# STM32.net
KiCad netlist of a schematic drawn in Altium Designer
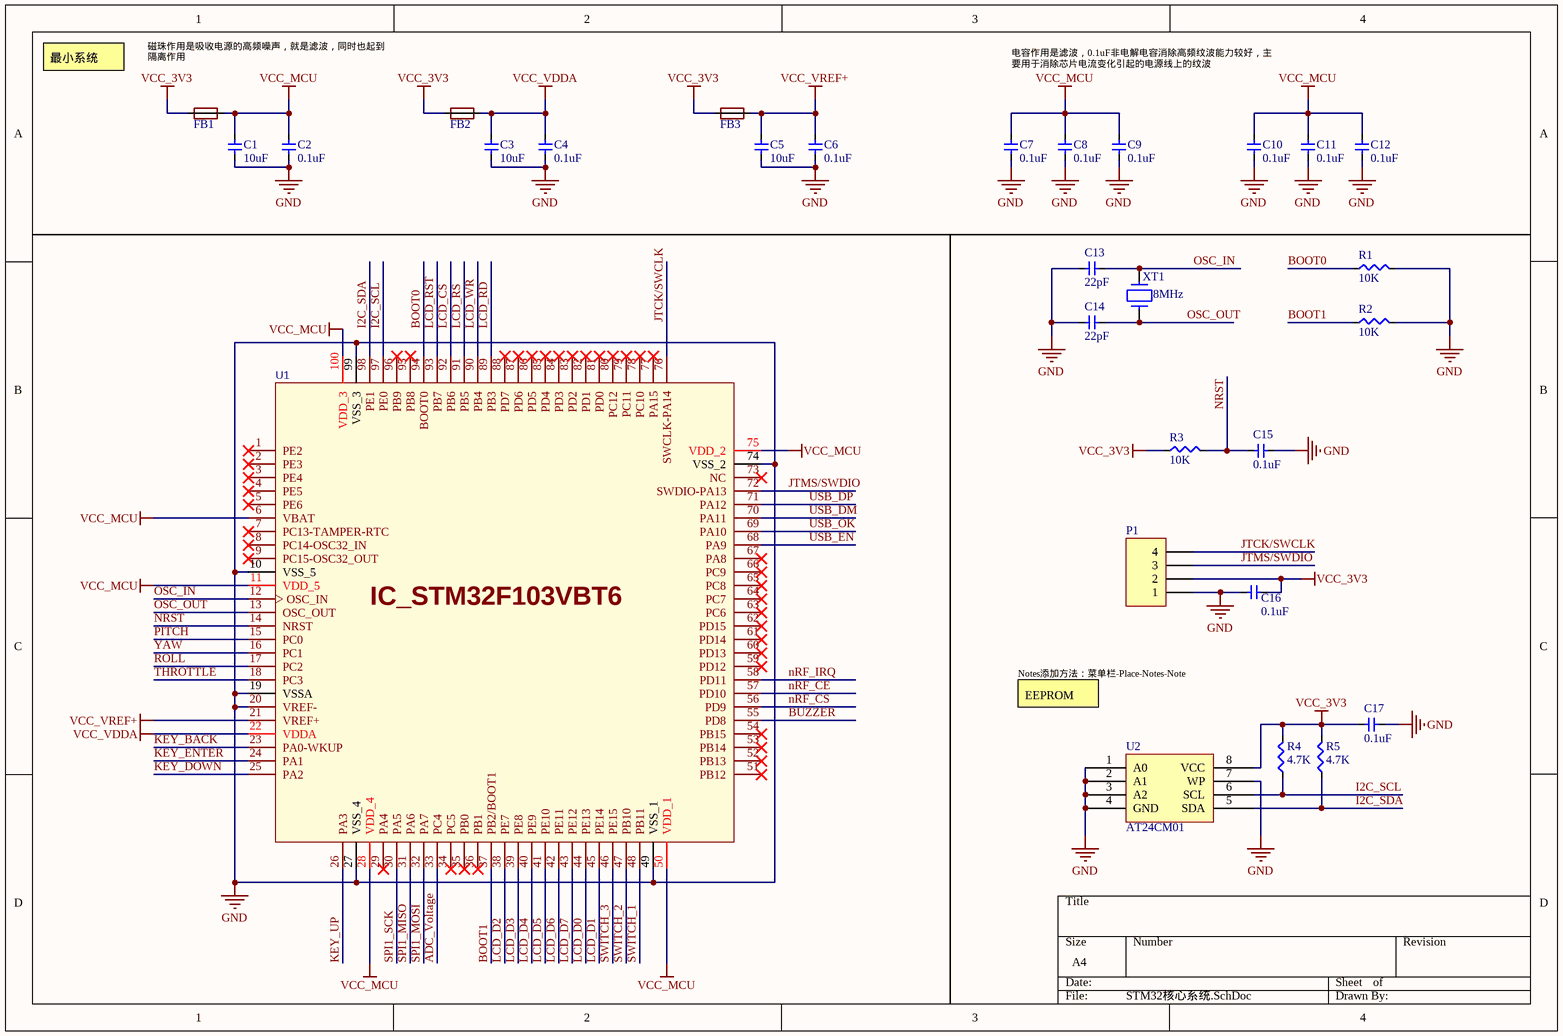
[diagram p0: STM32核心系统.SchDoc]

(export (version "E")
  (design (tool "Eeschema 10.0.6"))
  (components
    (comp (ref "C1")
      (value "10uF")
      (footprint "C 0603_L")
      (description "电容")
      (libsource (lib "SCHLIB") (part "CX_CAP"))
    )
    (comp (ref "C2")
      (value "0.1uF")
      (footprint "C 0603_L")
      (description "电容")
      (libsource (lib "SCHLIB") (part "CX_CAP"))
    )
    (comp (ref "C3")
      (value "10uF")
      (footprint "C 0603_L")
      (description "电容")
      (libsource (lib "SCHLIB") (part "CX_CAP"))
    )
    (comp (ref "C4")
      (value "0.1uF")
      (footprint "C 0603_L")
      (description "电容")
      (libsource (lib "SCHLIB") (part "CX_CAP"))
    )
    (comp (ref "C5")
      (value "10uF")
      (footprint "C 0603_L")
      (description "电容")
      (libsource (lib "SCHLIB") (part "CX_CAP"))
    )
    (comp (ref "C6")
      (value "0.1uF")
      (footprint "C 0603_L")
      (description "电容")
      (libsource (lib "SCHLIB") (part "CX_CAP"))
    )
    (comp (ref "C7")
      (value "0.1uF")
      (footprint "C 0603_L")
      (description "电容")
      (libsource (lib "SCHLIB") (part "CX_CAP"))
    )
    (comp (ref "C8")
      (value "0.1uF")
      (footprint "C 0603_L")
      (description "电容")
      (libsource (lib "SCHLIB") (part "CX_CAP"))
    )
    (comp (ref "C9")
      (value "0.1uF")
      (footprint "C 0603_L")
      (description "电容")
      (libsource (lib "SCHLIB") (part "CX_CAP"))
    )
    (comp (ref "C10")
      (value "0.1uF")
      (footprint "C 0603_L")
      (description "电容")
      (libsource (lib "SCHLIB") (part "CX_CAP"))
    )
    (comp (ref "C11")
      (value "0.1uF")
      (footprint "C 0603_L")
      (description "电容")
      (libsource (lib "SCHLIB") (part "CX_CAP"))
    )
    (comp (ref "C12")
      (value "0.1uF")
      (footprint "C 0603_L")
      (description "电容")
      (libsource (lib "SCHLIB") (part "CX_CAP"))
    )
    (comp (ref "C13")
      (value "22pF")
      (footprint "C 0603_L")
      (description "电容")
      (libsource (lib "SCHLIB") (part "CX_CAP"))
    )
    (comp (ref "C14")
      (value "22pF")
      (footprint "C 0603_L")
      (description "电容")
      (libsource (lib "SCHLIB") (part "CX_CAP"))
    )
    (comp (ref "C15")
      (value "0.1uF")
      (footprint "C 0603_L")
      (description "电容")
      (libsource (lib "SCHLIB") (part "CX_CAP"))
    )
    (comp (ref "C16")
      (value "0.1uF")
      (footprint "C 0603_L")
      (description "电容")
      (libsource (lib "SCHLIB") (part "CX_CAP"))
    )
    (comp (ref "C17")
      (value "0.1uF")
      (footprint "C 0603_L")
      (description "电容")
      (libsource (lib "SCHLIB") (part "CX_CAP"))
    )
    (comp (ref "FB1")
      (value "FB_BEAD")
      (footprint "FB 0603_L")
      (description "磁珠")
      (libsource (lib "MySCHLIB") (part "FB_BEAD"))
    )
    (comp (ref "FB2")
      (value "FB_BEAD")
      (footprint "FB 0603_L")
      (description "磁珠")
      (libsource (lib "MySCHLIB") (part "FB_BEAD"))
    )
    (comp (ref "FB3")
      (value "FB_BEAD")
      (footprint "FB 0603_L")
      (description "磁珠")
      (libsource (lib "MySCHLIB") (part "FB_BEAD"))
    )
    (comp (ref "P1")
      (value "Header 4")
      (footprint "XH2.54-WI-4P")
      (description "Header, 4-Pin")
      (fields (field (name "PUBLISHER") "Altium Limited"))
      (libsource (lib "Miscellaneous Connectors") (part "Header 4"))
    )
    (comp (ref "R1")
      (value "10K")
      (footprint "R 0603_L")
      (description "电阻")
      (libsource (lib "SCHLIB") (part "RX_RES"))
    )
    (comp (ref "R2")
      (value "10K")
      (footprint "R 0603_L")
      (description "电阻")
      (libsource (lib "SCHLIB") (part "RX_RES"))
    )
    (comp (ref "R3")
      (value "10K")
      (footprint "R 0603_L")
      (description "电阻")
      (libsource (lib "SCHLIB") (part "RX_RES"))
    )
    (comp (ref "R4")
      (value "4.7K")
      (footprint "R 0603_L")
      (description "电阻")
      (libsource (lib "SCHLIB") (part "RX_RES"))
    )
    (comp (ref "R5")
      (value "4.7K")
      (footprint "R 0603_L")
      (description "电阻")
      (libsource (lib "SCHLIB") (part "RX_RES"))
    )
    (comp (ref "U1")
      (value "IC_STM32F103VBT6")
      (footprint "LQFP100 14x14_M")
      (description "STM32单片机")
      (fields
        (field (name "BOM_SUPPLIER PART") "C8314")
        (field (name "BOM_MANUFACTURER PART") "STM32F103VBT6")
      )
      (libsource (lib "SCHLIB") (part "IC_STM32F103VBT6"))
    )
    (comp (ref "U2")
      (value "AT24CM01")
      (footprint "SOIC-8")
      (description "存储芯片")
      (libsource (lib "SCHLIB") (part "IC_AT24C02"))
    )
    (comp (ref "XT1")
      (value "8MHz")
      (footprint "OSC 5032-2P")
      (description "2P晶振")
      (fields (field (name "Comment") "XT_CRYSTAL2P"))
      (libsource (lib "SCHLIB") (part "XT_CRYSTAL2P"))
    )
  )
  (nets
    (net (code "1") (name "/ADC_Voltage") (class "Default")
      (node (ref "U1") (pin "33") (pinfunction "PC4_33") (pintype "passive"))
    )
    (net (code "2") (name "/BOOT0") (class "Default")
      (node (ref "R1") (pin "1") (pinfunction "1_1") (pintype "passive"))
      (node (ref "U1") (pin "94") (pinfunction "BOOT0_94") (pintype "passive"))
    )
    (net (code "3") (name "/BOOT1") (class "Default")
      (node (ref "R2") (pin "1") (pinfunction "1_1") (pintype "passive"))
      (node (ref "U1") (pin "37") (pinfunction "PB2/BOOT1_37") (pintype "passive"))
    )
    (net (code "4") (name "/BUZZER") (class "Default")
      (node (ref "U1") (pin "55") (pinfunction "PD8_55") (pintype "passive"))
    )
    (net (code "5") (name "/I2C_SCL") (class "Default")
      (node (ref "R4") (pin "1") (pinfunction "1_1") (pintype "passive"))
      (node (ref "U1") (pin "97") (pinfunction "PE0_97") (pintype "passive"))
      (node (ref "U2") (pin "6") (pinfunction "SCL_6") (pintype "passive"))
    )
    (net (code "6") (name "/I2C_SDA") (class "Default")
      (node (ref "R5") (pin "1") (pinfunction "1_1") (pintype "passive"))
      (node (ref "U1") (pin "98") (pinfunction "PE1_98") (pintype "passive"))
      (node (ref "U2") (pin "5") (pinfunction "SDA_5") (pintype "passive"))
    )
    (net (code "7") (name "/JTCK{slash}SWCLK") (class "Default")
      (node (ref "P1") (pin "4") (pinfunction "4_4") (pintype "passive"))
      (node (ref "U1") (pin "76") (pinfunction "SWCLK-PA14_76") (pintype "passive"))
    )
    (net (code "8") (name "/JTMS{slash}SWDIO") (class "Default")
      (node (ref "P1") (pin "3") (pinfunction "3_3") (pintype "passive"))
      (node (ref "U1") (pin "72") (pinfunction "SWDIO-PA13_72") (pintype "passive"))
    )
    (net (code "9") (name "/KEY_BACK") (class "Default")
      (node (ref "U1") (pin "23") (pinfunction "PA0-WKUP_23") (pintype "passive"))
    )
    (net (code "10") (name "/KEY_DOWN") (class "Default")
      (node (ref "U1") (pin "25") (pinfunction "PA2_25") (pintype "passive"))
    )
    (net (code "11") (name "/KEY_ENTER") (class "Default")
      (node (ref "U1") (pin "24") (pinfunction "PA1_24") (pintype "passive"))
    )
    (net (code "12") (name "/KEY_UP") (class "Default")
      (node (ref "U1") (pin "26") (pinfunction "PA3_26") (pintype "passive"))
    )
    (net (code "13") (name "/LCD_CS") (class "Default")
      (node (ref "U1") (pin "92") (pinfunction "PB6_92") (pintype "passive"))
    )
    (net (code "14") (name "/LCD_D0") (class "Default")
      (node (ref "U1") (pin "44") (pinfunction "PE13_44") (pintype "passive"))
    )
    (net (code "15") (name "/LCD_D1") (class "Default")
      (node (ref "U1") (pin "45") (pinfunction "PE14_45") (pintype "passive"))
    )
    (net (code "16") (name "/LCD_D2") (class "Default")
      (node (ref "U1") (pin "38") (pinfunction "PE7_38") (pintype "passive"))
    )
    (net (code "17") (name "/LCD_D3") (class "Default")
      (node (ref "U1") (pin "39") (pinfunction "PE8_39") (pintype "passive"))
    )
    (net (code "18") (name "/LCD_D4") (class "Default")
      (node (ref "U1") (pin "40") (pinfunction "PE9_40") (pintype "passive"))
    )
    (net (code "19") (name "/LCD_D5") (class "Default")
      (node (ref "U1") (pin "41") (pinfunction "PE10_41") (pintype "passive"))
    )
    (net (code "20") (name "/LCD_D6") (class "Default")
      (node (ref "U1") (pin "42") (pinfunction "PE11_42") (pintype "passive"))
    )
    (net (code "21") (name "/LCD_D7") (class "Default")
      (node (ref "U1") (pin "43") (pinfunction "PE12_43") (pintype "passive"))
    )
    (net (code "22") (name "/LCD_RD") (class "Default")
      (node (ref "U1") (pin "89") (pinfunction "PB3_89") (pintype "passive"))
    )
    (net (code "23") (name "/LCD_RS") (class "Default")
      (node (ref "U1") (pin "91") (pinfunction "PB5_91") (pintype "passive"))
    )
    (net (code "24") (name "/LCD_RST") (class "Default")
      (node (ref "U1") (pin "93") (pinfunction "PB7_93") (pintype "passive"))
    )
    (net (code "25") (name "/LCD_WR") (class "Default")
      (node (ref "U1") (pin "90") (pinfunction "PB4_90") (pintype "passive"))
    )
    (net (code "26") (name "/NRST") (class "Default")
      (node (ref "C15") (pin "1") (pinfunction "1_1") (pintype "passive"))
      (node (ref "R3") (pin "2") (pinfunction "2_2") (pintype "passive"))
      (node (ref "U1") (pin "14") (pinfunction "NRST_14") (pintype "passive"))
    )
    (net (code "27") (name "/OSC_IN") (class "Default")
      (node (ref "C13") (pin "2") (pinfunction "2_2") (pintype "passive"))
      (node (ref "U1") (pin "12") (pinfunction "OSC_IN_12") (pintype "passive"))
      (node (ref "XT1") (pin "2") (pinfunction "2_2") (pintype "passive"))
    )
    (net (code "28") (name "/OSC_OUT") (class "Default")
      (node (ref "C14") (pin "2") (pinfunction "2_2") (pintype "passive"))
      (node (ref "U1") (pin "13") (pinfunction "OSC_OUT_13") (pintype "passive"))
      (node (ref "XT1") (pin "1") (pinfunction "1_1") (pintype "passive"))
    )
    (net (code "29") (name "/PITCH") (class "Default")
      (node (ref "U1") (pin "15") (pinfunction "PC0_15") (pintype "passive"))
    )
    (net (code "30") (name "/ROLL") (class "Default")
      (node (ref "U1") (pin "17") (pinfunction "PC2_17") (pintype "passive"))
    )
    (net (code "31") (name "/SPI1_MISO") (class "Default")
      (node (ref "U1") (pin "31") (pinfunction "PA6_31") (pintype "passive"))
    )
    (net (code "32") (name "/SPI1_MOSI") (class "Default")
      (node (ref "U1") (pin "32") (pinfunction "PA7_32") (pintype "passive"))
    )
    (net (code "33") (name "/SPI1_SCK") (class "Default")
      (node (ref "U1") (pin "30") (pinfunction "PA5_30") (pintype "passive"))
    )
    (net (code "34") (name "/SWITCH_1") (class "Default")
      (node (ref "U1") (pin "48") (pinfunction "PB11_48") (pintype "passive"))
    )
    (net (code "35") (name "/SWITCH_2") (class "Default")
      (node (ref "U1") (pin "47") (pinfunction "PB10_47") (pintype "passive"))
    )
    (net (code "36") (name "/SWITCH_3") (class "Default")
      (node (ref "U1") (pin "46") (pinfunction "PE15_46") (pintype "passive"))
    )
    (net (code "37") (name "/THROTTLE") (class "Default")
      (node (ref "U1") (pin "18") (pinfunction "PC3_18") (pintype "passive"))
    )
    (net (code "38") (name "/USB_DM") (class "Default")
      (node (ref "U1") (pin "70") (pinfunction "PA11_70") (pintype "passive"))
    )
    (net (code "39") (name "/USB_DP") (class "Default")
      (node (ref "U1") (pin "71") (pinfunction "PA12_71") (pintype "passive"))
    )
    (net (code "40") (name "/USB_EN") (class "Default")
      (node (ref "U1") (pin "68") (pinfunction "PA9_68") (pintype "passive"))
    )
    (net (code "41") (name "/USB_OK") (class "Default")
      (node (ref "U1") (pin "69") (pinfunction "PA10_69") (pintype "passive"))
    )
    (net (code "42") (name "/YAW") (class "Default")
      (node (ref "U1") (pin "16") (pinfunction "PC1_16") (pintype "passive"))
    )
    (net (code "43") (name "/nRF_CE") (class "Default")
      (node (ref "U1") (pin "57") (pinfunction "PD10_57") (pintype "passive"))
    )
    (net (code "44") (name "/nRF_CS") (class "Default")
      (node (ref "U1") (pin "56") (pinfunction "PD9_56") (pintype "passive"))
    )
    (net (code "45") (name "/nRF_IRQ") (class "Default")
      (node (ref "U1") (pin "58") (pinfunction "PD11_58") (pintype "passive"))
    )
    (net (code "46") (name "GND") (class "Default")
      (node (ref "C1") (pin "2") (pinfunction "2_2") (pintype "passive"))
      (node (ref "C10") (pin "2") (pinfunction "2_2") (pintype "passive"))
      (node (ref "C11") (pin "2") (pinfunction "2_2") (pintype "passive"))
      (node (ref "C12") (pin "2") (pinfunction "2_2") (pintype "passive"))
      (node (ref "C13") (pin "1") (pinfunction "1_1") (pintype "passive"))
      (node (ref "C14") (pin "1") (pinfunction "1_1") (pintype "passive"))
      (node (ref "C15") (pin "2") (pinfunction "2_2") (pintype "passive"))
      (node (ref "C16") (pin "1") (pinfunction "1_1") (pintype "passive"))
      (node (ref "C17") (pin "2") (pinfunction "2_2") (pintype "passive"))
      (node (ref "C2") (pin "2") (pinfunction "2_2") (pintype "passive"))
      (node (ref "C3") (pin "2") (pinfunction "2_2") (pintype "passive"))
      (node (ref "C4") (pin "2") (pinfunction "2_2") (pintype "passive"))
      (node (ref "C5") (pin "2") (pinfunction "2_2") (pintype "passive"))
      (node (ref "C6") (pin "2") (pinfunction "2_2") (pintype "passive"))
      (node (ref "C7") (pin "2") (pinfunction "2_2") (pintype "passive"))
      (node (ref "C8") (pin "2") (pinfunction "2_2") (pintype "passive"))
      (node (ref "C9") (pin "2") (pinfunction "2_2") (pintype "passive"))
      (node (ref "P1") (pin "1") (pinfunction "1_1") (pintype "passive"))
      (node (ref "R1") (pin "2") (pinfunction "2_2") (pintype "passive"))
      (node (ref "R2") (pin "2") (pinfunction "2_2") (pintype "passive"))
      (node (ref "U1") (pin "10") (pinfunction "VSS_5_10") (pintype "passive"))
      (node (ref "U1") (pin "19") (pinfunction "VSSA_19") (pintype "passive"))
      (node (ref "U1") (pin "20") (pinfunction "VREF-_20") (pintype "passive"))
      (node (ref "U1") (pin "27") (pinfunction "VSS_4_27") (pintype "passive"))
      (node (ref "U1") (pin "49") (pinfunction "VSS_1_49") (pintype "passive"))
      (node (ref "U1") (pin "74") (pinfunction "VSS_2_74") (pintype "passive"))
      (node (ref "U1") (pin "99") (pinfunction "VSS_3_99") (pintype "passive"))
      (node (ref "U2") (pin "1") (pinfunction "A0_1") (pintype "passive"))
      (node (ref "U2") (pin "2") (pinfunction "A1_2") (pintype "passive"))
      (node (ref "U2") (pin "3") (pinfunction "A2_3") (pintype "passive"))
      (node (ref "U2") (pin "4") (pinfunction "GND_4") (pintype "passive"))
      (node (ref "U2") (pin "7") (pinfunction "WP_7") (pintype "passive"))
    )
    (net (code "47") (name "VCC_3V3") (class "Default")
      (node (ref "C16") (pin "2") (pinfunction "2_2") (pintype "passive"))
      (node (ref "C17") (pin "1") (pinfunction "1_1") (pintype "passive"))
      (node (ref "FB1") (pin "2") (pinfunction "2_2") (pintype "passive"))
      (node (ref "FB2") (pin "2") (pinfunction "2_2") (pintype "passive"))
      (node (ref "FB3") (pin "2") (pinfunction "2_2") (pintype "passive"))
      (node (ref "P1") (pin "2") (pinfunction "2_2") (pintype "passive"))
      (node (ref "R3") (pin "1") (pinfunction "1_1") (pintype "passive"))
      (node (ref "R4") (pin "2") (pinfunction "2_2") (pintype "passive"))
      (node (ref "R5") (pin "2") (pinfunction "2_2") (pintype "passive"))
      (node (ref "U2") (pin "8") (pinfunction "VCC_8") (pintype "passive"))
    )
    (net (code "48") (name "VCC_MCU") (class "Default")
      (node (ref "C1") (pin "1") (pinfunction "1_1") (pintype "passive"))
      (node (ref "C10") (pin "1") (pinfunction "1_1") (pintype "passive"))
      (node (ref "C11") (pin "1") (pinfunction "1_1") (pintype "passive"))
      (node (ref "C12") (pin "1") (pinfunction "1_1") (pintype "passive"))
      (node (ref "C2") (pin "1") (pinfunction "1_1") (pintype "passive"))
      (node (ref "C7") (pin "1") (pinfunction "1_1") (pintype "passive"))
      (node (ref "C8") (pin "1") (pinfunction "1_1") (pintype "passive"))
      (node (ref "C9") (pin "1") (pinfunction "1_1") (pintype "passive"))
      (node (ref "FB1") (pin "1") (pinfunction "1_1") (pintype "passive"))
      (node (ref "U1") (pin "100") (pinfunction "VDD_3_100") (pintype "passive"))
      (node (ref "U1") (pin "11") (pinfunction "VDD_5_11") (pintype "passive"))
      (node (ref "U1") (pin "28") (pinfunction "VDD_4_28") (pintype "passive"))
      (node (ref "U1") (pin "50") (pinfunction "VDD_1_50") (pintype "passive"))
      (node (ref "U1") (pin "6") (pinfunction "VBAT_6") (pintype "passive"))
      (node (ref "U1") (pin "75") (pinfunction "VDD_2_75") (pintype "passive"))
    )
    (net (code "49") (name "VCC_VDDA") (class "Default")
      (node (ref "C3") (pin "1") (pinfunction "1_1") (pintype "passive"))
      (node (ref "C4") (pin "1") (pinfunction "1_1") (pintype "passive"))
      (node (ref "FB2") (pin "1") (pinfunction "1_1") (pintype "passive"))
      (node (ref "U1") (pin "22") (pinfunction "VDDA_22") (pintype "passive"))
    )
    (net (code "50") (name "VCC_VREF+") (class "Default")
      (node (ref "C5") (pin "1") (pinfunction "1_1") (pintype "passive"))
      (node (ref "C6") (pin "1") (pinfunction "1_1") (pintype "passive"))
      (node (ref "FB3") (pin "1") (pinfunction "1_1") (pintype "passive"))
      (node (ref "U1") (pin "21") (pinfunction "VREF+_21") (pintype "passive"))
    )
    (net (code "51") (name "unconnected-(U1-NC-Pad73)") (class "Default")
      (node (ref "U1") (pin "73") (pinfunction "NC_73") (pintype "passive+no_connect"))
    )
    (net (code "52") (name "unconnected-(U1-PA4-Pad29)") (class "Default")
      (node (ref "U1") (pin "29") (pinfunction "PA4_29") (pintype "passive+no_connect"))
    )
    (net (code "53") (name "unconnected-(U1-PA8-Pad67)") (class "Default")
      (node (ref "U1") (pin "67") (pinfunction "PA8_67") (pintype "passive+no_connect"))
    )
    (net (code "54") (name "unconnected-(U1-PA15-Pad77)") (class "Default")
      (node (ref "U1") (pin "77") (pinfunction "PA15_77") (pintype "passive+no_connect"))
    )
    (net (code "55") (name "unconnected-(U1-PB0-Pad35)") (class "Default")
      (node (ref "U1") (pin "35") (pinfunction "PB0_35") (pintype "passive+no_connect"))
    )
    (net (code "56") (name "unconnected-(U1-PB1-Pad36)") (class "Default")
      (node (ref "U1") (pin "36") (pinfunction "PB1_36") (pintype "passive+no_connect"))
    )
    (net (code "57") (name "unconnected-(U1-PB8-Pad95)") (class "Default")
      (node (ref "U1") (pin "95") (pinfunction "PB8_95") (pintype "passive+no_connect"))
    )
    (net (code "58") (name "unconnected-(U1-PB9-Pad96)") (class "Default")
      (node (ref "U1") (pin "96") (pinfunction "PB9_96") (pintype "passive+no_connect"))
    )
    (net (code "59") (name "unconnected-(U1-PB12-Pad51)") (class "Default")
      (node (ref "U1") (pin "51") (pinfunction "PB12_51") (pintype "passive+no_connect"))
    )
    (net (code "60") (name "unconnected-(U1-PB13-Pad52)") (class "Default")
      (node (ref "U1") (pin "52") (pinfunction "PB13_52") (pintype "passive+no_connect"))
    )
    (net (code "61") (name "unconnected-(U1-PB14-Pad53)") (class "Default")
      (node (ref "U1") (pin "53") (pinfunction "PB14_53") (pintype "passive+no_connect"))
    )
    (net (code "62") (name "unconnected-(U1-PB15-Pad54)") (class "Default")
      (node (ref "U1") (pin "54") (pinfunction "PB15_54") (pintype "passive+no_connect"))
    )
    (net (code "63") (name "unconnected-(U1-PC5-Pad34)") (class "Default")
      (node (ref "U1") (pin "34") (pinfunction "PC5_34") (pintype "passive+no_connect"))
    )
    (net (code "64") (name "unconnected-(U1-PC6-Pad63)") (class "Default")
      (node (ref "U1") (pin "63") (pinfunction "PC6_63") (pintype "passive+no_connect"))
    )
    (net (code "65") (name "unconnected-(U1-PC7-Pad64)") (class "Default")
      (node (ref "U1") (pin "64") (pinfunction "PC7_64") (pintype "passive+no_connect"))
    )
    (net (code "66") (name "unconnected-(U1-PC8-Pad65)") (class "Default")
      (node (ref "U1") (pin "65") (pinfunction "PC8_65") (pintype "passive+no_connect"))
    )
    (net (code "67") (name "unconnected-(U1-PC9-Pad66)") (class "Default")
      (node (ref "U1") (pin "66") (pinfunction "PC9_66") (pintype "passive+no_connect"))
    )
    (net (code "68") (name "unconnected-(U1-PC10-Pad78)") (class "Default")
      (node (ref "U1") (pin "78") (pinfunction "PC10_78") (pintype "passive+no_connect"))
    )
    (net (code "69") (name "unconnected-(U1-PC11-Pad79)") (class "Default")
      (node (ref "U1") (pin "79") (pinfunction "PC11_79") (pintype "passive+no_connect"))
    )
    (net (code "70") (name "unconnected-(U1-PC12-Pad80)") (class "Default")
      (node (ref "U1") (pin "80") (pinfunction "PC12_80") (pintype "passive+no_connect"))
    )
    (net (code "71") (name "unconnected-(U1-PC13-TAMPER-RTC-Pad7)") (class "Default")
      (node (ref "U1") (pin "7") (pinfunction "PC13-TAMPER-RTC_7") (pintype "passive+no_connect"))
    )
    (net (code "72") (name "unconnected-(U1-PC14-OSC32_IN-Pad8)") (class "Default")
      (node (ref "U1") (pin "8") (pinfunction "PC14-OSC32_IN_8") (pintype "passive+no_connect"))
    )
    (net (code "73") (name "unconnected-(U1-PC15-OSC32_OUT-Pad9)") (class "Default")
      (node (ref "U1") (pin "9") (pinfunction "PC15-OSC32_OUT_9") (pintype "passive+no_connect"))
    )
    (net (code "74") (name "unconnected-(U1-PD0-Pad81)") (class "Default")
      (node (ref "U1") (pin "81") (pinfunction "PD0_81") (pintype "passive+no_connect"))
    )
    (net (code "75") (name "unconnected-(U1-PD1-Pad82)") (class "Default")
      (node (ref "U1") (pin "82") (pinfunction "PD1_82") (pintype "passive+no_connect"))
    )
    (net (code "76") (name "unconnected-(U1-PD2-Pad83)") (class "Default")
      (node (ref "U1") (pin "83") (pinfunction "PD2_83") (pintype "passive+no_connect"))
    )
    (net (code "77") (name "unconnected-(U1-PD3-Pad84)") (class "Default")
      (node (ref "U1") (pin "84") (pinfunction "PD3_84") (pintype "passive+no_connect"))
    )
    (net (code "78") (name "unconnected-(U1-PD4-Pad85)") (class "Default")
      (node (ref "U1") (pin "85") (pinfunction "PD4_85") (pintype "passive+no_connect"))
    )
    (net (code "79") (name "unconnected-(U1-PD5-Pad86)") (class "Default")
      (node (ref "U1") (pin "86") (pinfunction "PD5_86") (pintype "passive+no_connect"))
    )
    (net (code "80") (name "unconnected-(U1-PD6-Pad87)") (class "Default")
      (node (ref "U1") (pin "87") (pinfunction "PD6_87") (pintype "passive+no_connect"))
    )
    (net (code "81") (name "unconnected-(U1-PD7-Pad88)") (class "Default")
      (node (ref "U1") (pin "88") (pinfunction "PD7_88") (pintype "passive+no_connect"))
    )
    (net (code "82") (name "unconnected-(U1-PD12-Pad59)") (class "Default")
      (node (ref "U1") (pin "59") (pinfunction "PD12_59") (pintype "passive+no_connect"))
    )
    (net (code "83") (name "unconnected-(U1-PD13-Pad60)") (class "Default")
      (node (ref "U1") (pin "60") (pinfunction "PD13_60") (pintype "passive+no_connect"))
    )
    (net (code "84") (name "unconnected-(U1-PD14-Pad61)") (class "Default")
      (node (ref "U1") (pin "61") (pinfunction "PD14_61") (pintype "passive+no_connect"))
    )
    (net (code "85") (name "unconnected-(U1-PD15-Pad62)") (class "Default")
      (node (ref "U1") (pin "62") (pinfunction "PD15_62") (pintype "passive+no_connect"))
    )
    (net (code "86") (name "unconnected-(U1-PE2-Pad1)") (class "Default")
      (node (ref "U1") (pin "1") (pinfunction "PE2_1") (pintype "passive+no_connect"))
    )
    (net (code "87") (name "unconnected-(U1-PE3-Pad2)") (class "Default")
      (node (ref "U1") (pin "2") (pinfunction "PE3_2") (pintype "passive+no_connect"))
    )
    (net (code "88") (name "unconnected-(U1-PE4-Pad3)") (class "Default")
      (node (ref "U1") (pin "3") (pinfunction "PE4_3") (pintype "passive+no_connect"))
    )
    (net (code "89") (name "unconnected-(U1-PE5-Pad4)") (class "Default")
      (node (ref "U1") (pin "4") (pinfunction "PE5_4") (pintype "passive+no_connect"))
    )
    (net (code "90") (name "unconnected-(U1-PE6-Pad5)") (class "Default")
      (node (ref "U1") (pin "5") (pinfunction "PE6_5") (pintype "passive+no_connect"))
    )
  )
)
